# IoTKitV3th-ohneGND.net
KiCad netlist of a schematic drawn in EAGLE
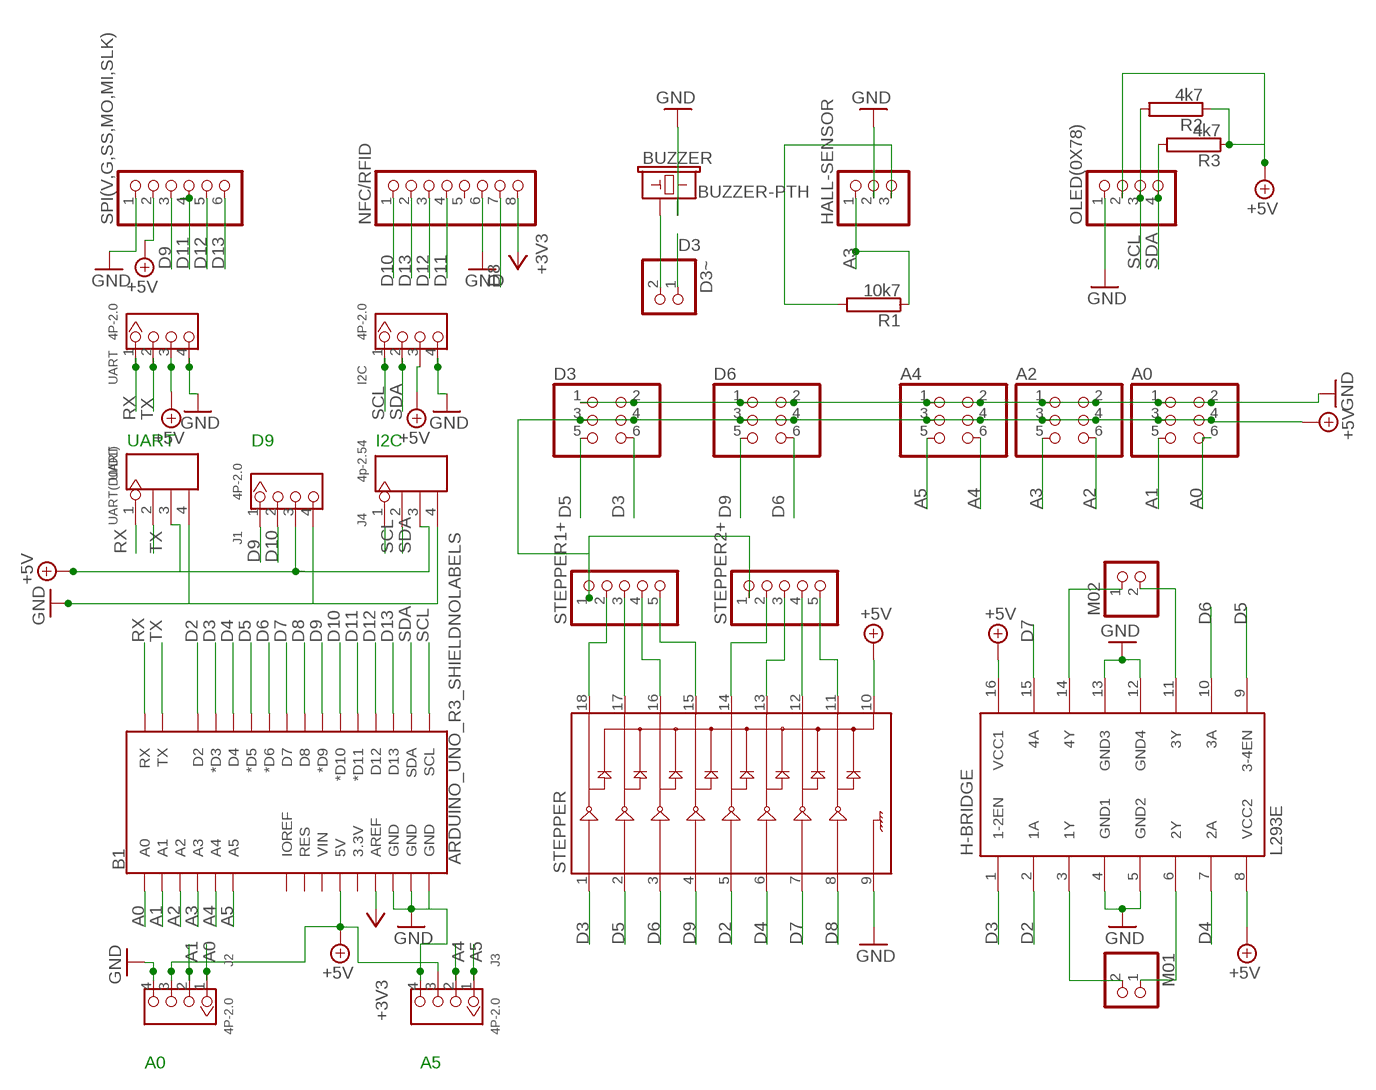
[diagram p0: schematic, sheet 1]

(export (version "E")
  (design (tool "Eeschema 10.0.6"))
  (components
    (comp (ref "A0")
      (value "PINHD-2X3")
      (footprint "eagle-import:2X03")
      (libsource (lib "eagle-import") (part "PINHD-2X3"))
    )
    (comp (ref "A2")
      (value "PINHD-2X3")
      (footprint "eagle-import:2X03")
      (libsource (lib "eagle-import") (part "PINHD-2X3"))
    )
    (comp (ref "A4")
      (value "PINHD-2X3")
      (footprint "eagle-import:2X03")
      (libsource (lib "eagle-import") (part "PINHD-2X3"))
    )
    (comp (ref "B1")
      (value "ARDUINO_UNO_R3_SHIELDNOLABELS")
      (footprint "eagle-import:UNO_R3_SHIELD_NOLABELS")
      (libsource (lib "eagle-import") (part "ARDUINO_UNO_R3_SHIELDNOLABELS"))
    )
    (comp (ref "BUZZER")
      (value "BUZZER-PTH")
      (footprint "eagle-import:BUZZER-12MM")
      (libsource (lib "eagle-import") (part "BUZZER-PTH"))
    )
    (comp (ref "D3")
      (value "PINHD-2X3")
      (footprint "eagle-import:2X03")
      (libsource (lib "eagle-import") (part "PINHD-2X3"))
    )
    (comp (ref "D3~")
      (value "PINHD-1X2")
      (footprint "eagle-import:1X02")
      (libsource (lib "eagle-import") (part "PINHD-1X2"))
    )
    (comp (ref "D6")
      (value "PINHD-2X3")
      (footprint "eagle-import:2X03")
      (libsource (lib "eagle-import") (part "PINHD-2X3"))
    )
    (comp (ref "H-BRIDGE")
      (value "L293E")
      (footprint "eagle-import:DIL16")
      (fields (field (name "MF") "Arrow Electronics"))
      (libsource (lib "eagle-import") (part "L293E"))
    )
    (comp (ref "HALL-SENSOR")
      (value "PINHD-1X3")
      (footprint "eagle-import:1X03")
      (libsource (lib "eagle-import") (part "PINHD-1X3"))
    )
    (comp (ref "I2C")
      (value "4P-2.0")
      (footprint "eagle-import:HW4-2.0")
      (libsource (lib "eagle-import") (part "GROVE-CONNECTOR-DIP(4P-2.0)"))
    )
    (comp (ref "J1")
      (value "4P-2.0")
      (footprint "eagle-import:HW4-2.0")
      (libsource (lib "eagle-import") (part "GROVE-CONNECTOR-DIP(4P-2.0)"))
    )
    (comp (ref "J2")
      (value "4P-2.0")
      (footprint "eagle-import:HW4-2.0")
      (libsource (lib "eagle-import") (part "GROVE-CONNECTOR-DIP(4P-2.0)"))
    )
    (comp (ref "J3")
      (value "4P-2.0")
      (footprint "eagle-import:HW4-2.0")
      (libsource (lib "eagle-import") (part "GROVE-CONNECTOR-DIP(4P-2.0)"))
    )
    (comp (ref "J4")
      (value "4p-2.54")
      (footprint "eagle-import:H4-2.54")
      (fields (field (name "MPN") "P125-1104A0BS116A1"))
      (libsource (lib "eagle-import") (part "DIP-BLACK-MALE-HEADER-VERT(4P-2.54)"))
    )
    (comp (ref "M01")
      (value "PINHD-1X2")
      (footprint "eagle-import:1X02")
      (libsource (lib "eagle-import") (part "PINHD-1X2"))
    )
    (comp (ref "M02")
      (value "PINHD-1X2")
      (footprint "eagle-import:1X02")
      (libsource (lib "eagle-import") (part "PINHD-1X2"))
    )
    (comp (ref "NFC/RFID")
      (value "PINHD-1X8")
      (footprint "eagle-import:1X08")
      (libsource (lib "eagle-import") (part "PINHD-1X8"))
    )
    (comp (ref "OLED(0X78)")
      (value "PINHD-1X4")
      (footprint "eagle-import:1X04")
      (libsource (lib "eagle-import") (part "PINHD-1X4"))
    )
    (comp (ref "R1")
      (value "10k7")
      (footprint "eagle-import:CA0001")
      (libsource (lib "eagle-import") (part "RCA0001"))
    )
    (comp (ref "R2")
      (value "4k7")
      (footprint "eagle-import:CA0001")
      (libsource (lib "eagle-import") (part "RCA0001"))
    )
    (comp (ref "R3")
      (value "4k7")
      (footprint "eagle-import:CA0001")
      (libsource (lib "eagle-import") (part "RCA0001"))
    )
    (comp (ref "SPI(V,G,SS,MO,MI,SLK)")
      (value "PINHD-1X6")
      (footprint "eagle-import:1X06")
      (libsource (lib "eagle-import") (part "PINHD-1X6"))
    )
    (comp (ref "STEPPER")
      (value "ULN2803DIP")
      (footprint "eagle-import:DIL18")
      (libsource (lib "eagle-import") (part "ULN2803DIP"))
    )
    (comp (ref "STEPPER1+")
      (value "PINHD-1X5")
      (footprint "eagle-import:1X05")
      (libsource (lib "eagle-import") (part "PINHD-1X5"))
    )
    (comp (ref "STEPPER2+")
      (value "PINHD-1X5")
      (footprint "eagle-import:1X05")
      (libsource (lib "eagle-import") (part "PINHD-1X5"))
    )
    (comp (ref "UART")
      (value "4P-2.0")
      (footprint "eagle-import:HW4-2.0")
      (libsource (lib "eagle-import") (part "GROVE-CONNECTOR-DIP(4P-2.0)"))
    )
    (comp (ref "UART(D0/D1)")
      (value "UART")
      (footprint "eagle-import:H4-2.54")
      (fields (field (name "MPN") "P125-1104A0BS116A1"))
      (libsource (lib "eagle-import") (part "DIP-BLACK-MALE-HEADER-VERT(4P-2.54)"))
    )
  )
  (nets
    (net (code "1") (name "+3V3") (class "Default")
      (node (ref "B1") (pin "AREF") (pinfunction "AREF_AREF") (pintype "bidirectional"))
      (node (ref "NFC/RFID") (pin "8") (pinfunction "8_8") (pintype "passive"))
    )
    (net (code "2") (name "+5V") (class "Default")
      (node (ref "A0") (pin "3") (pinfunction "3_3") (pintype "passive"))
      (node (ref "A0") (pin "4") (pinfunction "4_4") (pintype "passive"))
      (node (ref "A2") (pin "3") (pinfunction "3_3") (pintype "passive"))
      (node (ref "A2") (pin "4") (pinfunction "4_4") (pintype "passive"))
      (node (ref "A4") (pin "3") (pinfunction "3_3") (pintype "passive"))
      (node (ref "A4") (pin "4") (pinfunction "4_4") (pintype "passive"))
      (node (ref "B1") (pin "5V") (pinfunction "5V_5V") (pintype "bidirectional"))
      (node (ref "D3") (pin "3") (pinfunction "3_3") (pintype "passive"))
      (node (ref "D3") (pin "4") (pinfunction "4_4") (pintype "passive"))
      (node (ref "D6") (pin "3") (pinfunction "3_3") (pintype "passive"))
      (node (ref "D6") (pin "4") (pinfunction "4_4") (pintype "passive"))
      (node (ref "H-BRIDGE") (pin "16") (pinfunction "VCC1_16") (pintype "power_in"))
      (node (ref "H-BRIDGE") (pin "8") (pinfunction "VCC2_8") (pintype "power_in"))
      (node (ref "I2C") (pin "3") (pinfunction "3_3") (pintype "bidirectional"))
      (node (ref "J1") (pin "3") (pinfunction "3_3") (pintype "bidirectional"))
      (node (ref "J2") (pin "3") (pinfunction "3_3") (pintype "bidirectional"))
      (node (ref "J3") (pin "3") (pinfunction "3_3") (pintype "bidirectional"))
      (node (ref "J4") (pin "3") (pinfunction "P$3_3") (pintype "bidirectional"))
      (node (ref "OLED(0X78)") (pin "2") (pinfunction "2_2") (pintype "passive"))
      (node (ref "R2") (pin "1") (pinfunction "1_1") (pintype "passive"))
      (node (ref "R3") (pin "1") (pinfunction "1_1") (pintype "passive"))
      (node (ref "SPI(V,G,SS,MO,MI,SLK)") (pin "2") (pinfunction "2_2") (pintype "passive"))
      (node (ref "STEPPER") (pin "10") (pinfunction "10_10") (pintype "bidirectional"))
      (node (ref "STEPPER1+") (pin "1") (pinfunction "1_1") (pintype "passive"))
      (node (ref "STEPPER2+") (pin "1") (pinfunction "1_1") (pintype "passive"))
      (node (ref "UART") (pin "3") (pinfunction "3_3") (pintype "bidirectional"))
      (node (ref "UART(D0/D1)") (pin "3") (pinfunction "P$3_3") (pintype "bidirectional"))
    )
    (net (code "3") (name "/A0") (class "Default")
      (node (ref "A0") (pin "6") (pinfunction "6_6") (pintype "passive"))
      (node (ref "B1") (pin "A0") (pinfunction "A0_A0") (pintype "bidirectional"))
      (node (ref "J2") (pin "1") (pinfunction "1_1") (pintype "bidirectional"))
    )
    (net (code "4") (name "/A1") (class "Default")
      (node (ref "A0") (pin "5") (pinfunction "5_5") (pintype "passive"))
      (node (ref "B1") (pin "A1") (pinfunction "A1_A1") (pintype "bidirectional"))
      (node (ref "J2") (pin "2") (pinfunction "2_2") (pintype "bidirectional"))
    )
    (net (code "5") (name "/A2") (class "Default")
      (node (ref "A2") (pin "6") (pinfunction "6_6") (pintype "passive"))
      (node (ref "B1") (pin "A2") (pinfunction "A2_A2") (pintype "bidirectional"))
    )
    (net (code "6") (name "/A3") (class "Default")
      (node (ref "A2") (pin "5") (pinfunction "5_5") (pintype "passive"))
      (node (ref "B1") (pin "A3") (pinfunction "A3_A3") (pintype "bidirectional"))
      (node (ref "HALL-SENSOR") (pin "1") (pinfunction "1_1") (pintype "passive"))
      (node (ref "R1") (pin "1") (pinfunction "1_1") (pintype "passive"))
    )
    (net (code "7") (name "/A4") (class "Default")
      (node (ref "A4") (pin "6") (pinfunction "6_6") (pintype "passive"))
      (node (ref "B1") (pin "A4") (pinfunction "A4_A4") (pintype "bidirectional"))
      (node (ref "J3") (pin "2") (pinfunction "2_2") (pintype "bidirectional"))
    )
    (net (code "8") (name "/A5") (class "Default")
      (node (ref "A4") (pin "5") (pinfunction "5_5") (pintype "passive"))
      (node (ref "B1") (pin "A5") (pinfunction "A5_A5") (pintype "bidirectional"))
      (node (ref "J3") (pin "1") (pinfunction "1_1") (pintype "bidirectional"))
    )
    (net (code "9") (name "/D2") (class "Default")
      (node (ref "B1") (pin "D2") (pinfunction "D2_D2") (pintype "bidirectional"))
      (node (ref "H-BRIDGE") (pin "2") (pinfunction "1A_2") (pintype "input"))
      (node (ref "STEPPER") (pin "5") (pinfunction "5_5") (pintype "bidirectional"))
    )
    (net (code "10") (name "/D3") (class "Default")
      (node (ref "B1") (pin "D3") (pinfunction "*D3_D3") (pintype "bidirectional"))
      (node (ref "D3") (pin "6") (pinfunction "6_6") (pintype "passive"))
      (node (ref "D3~") (pin "1") (pinfunction "1_1") (pintype "passive"))
      (node (ref "H-BRIDGE") (pin "1") (pinfunction "1-2EN_1") (pintype "input"))
      (node (ref "STEPPER") (pin "1") (pinfunction "1_1") (pintype "bidirectional"))
    )
    (net (code "11") (name "/D4") (class "Default")
      (node (ref "B1") (pin "D4") (pinfunction "D4_D4") (pintype "bidirectional"))
      (node (ref "H-BRIDGE") (pin "7") (pinfunction "2A_7") (pintype "input"))
      (node (ref "STEPPER") (pin "6") (pinfunction "6_6") (pintype "bidirectional"))
    )
    (net (code "12") (name "/D5") (class "Default")
      (node (ref "B1") (pin "D5") (pinfunction "*D5_D5") (pintype "bidirectional"))
      (node (ref "D3") (pin "5") (pinfunction "5_5") (pintype "passive"))
      (node (ref "H-BRIDGE") (pin "9") (pinfunction "3-4EN_9") (pintype "input"))
      (node (ref "STEPPER") (pin "2") (pinfunction "2_2") (pintype "bidirectional"))
    )
    (net (code "13") (name "/D6") (class "Default")
      (node (ref "B1") (pin "D6") (pinfunction "*D6_D6") (pintype "bidirectional"))
      (node (ref "D6") (pin "6") (pinfunction "6_6") (pintype "passive"))
      (node (ref "H-BRIDGE") (pin "10") (pinfunction "3A_10") (pintype "input"))
      (node (ref "STEPPER") (pin "3") (pinfunction "3_3") (pintype "bidirectional"))
    )
    (net (code "14") (name "/D7") (class "Default")
      (node (ref "B1") (pin "D7") (pinfunction "D7_D7") (pintype "bidirectional"))
      (node (ref "H-BRIDGE") (pin "15") (pinfunction "4A_15") (pintype "input"))
      (node (ref "STEPPER") (pin "7") (pinfunction "7_7") (pintype "bidirectional"))
    )
    (net (code "15") (name "/D8") (class "Default")
      (node (ref "B1") (pin "D8") (pinfunction "D8_D8") (pintype "bidirectional"))
      (node (ref "NFC/RFID") (pin "7") (pinfunction "7_7") (pintype "passive"))
      (node (ref "STEPPER") (pin "8") (pinfunction "8_8") (pintype "bidirectional"))
    )
    (net (code "16") (name "/D9") (class "Default")
      (node (ref "B1") (pin "D9") (pinfunction "*D9_D9") (pintype "bidirectional"))
      (node (ref "D6") (pin "5") (pinfunction "5_5") (pintype "passive"))
      (node (ref "J1") (pin "1") (pinfunction "1_1") (pintype "bidirectional"))
      (node (ref "SPI(V,G,SS,MO,MI,SLK)") (pin "3") (pinfunction "3_3") (pintype "passive"))
      (node (ref "STEPPER") (pin "4") (pinfunction "4_4") (pintype "bidirectional"))
    )
    (net (code "17") (name "/D10") (class "Default")
      (node (ref "B1") (pin "D10") (pinfunction "*D10_D10") (pintype "bidirectional"))
      (node (ref "J1") (pin "2") (pinfunction "2_2") (pintype "bidirectional"))
      (node (ref "NFC/RFID") (pin "1") (pinfunction "1_1") (pintype "passive"))
    )
    (net (code "18") (name "/D11") (class "Default")
      (node (ref "B1") (pin "D11") (pinfunction "*D11_D11") (pintype "bidirectional"))
      (node (ref "NFC/RFID") (pin "4") (pinfunction "4_4") (pintype "passive"))
      (node (ref "SPI(V,G,SS,MO,MI,SLK)") (pin "4") (pinfunction "4_4") (pintype "passive"))
    )
    (net (code "19") (name "/D12") (class "Default")
      (node (ref "B1") (pin "D12") (pinfunction "D12_D12") (pintype "bidirectional"))
      (node (ref "NFC/RFID") (pin "3") (pinfunction "3_3") (pintype "passive"))
      (node (ref "SPI(V,G,SS,MO,MI,SLK)") (pin "5") (pinfunction "5_5") (pintype "passive"))
    )
    (net (code "20") (name "/D13") (class "Default")
      (node (ref "B1") (pin "D13") (pinfunction "D13_D13") (pintype "bidirectional"))
      (node (ref "NFC/RFID") (pin "2") (pinfunction "2_2") (pintype "passive"))
      (node (ref "SPI(V,G,SS,MO,MI,SLK)") (pin "6") (pinfunction "6_6") (pintype "passive"))
    )
    (net (code "21") (name "/RX") (class "Default")
      (node (ref "B1") (pin "RX") (pinfunction "RX_RX") (pintype "bidirectional"))
      (node (ref "UART") (pin "1") (pinfunction "1_1") (pintype "bidirectional"))
      (node (ref "UART(D0/D1)") (pin "1") (pinfunction "P$1_1") (pintype "bidirectional"))
    )
    (net (code "22") (name "/SCL") (class "Default")
      (node (ref "B1") (pin "SCL") (pinfunction "SCL_SCL") (pintype "bidirectional"))
      (node (ref "I2C") (pin "1") (pinfunction "1_1") (pintype "bidirectional"))
      (node (ref "J4") (pin "1") (pinfunction "P$1_1") (pintype "bidirectional"))
      (node (ref "OLED(0X78)") (pin "3") (pinfunction "3_3") (pintype "passive"))
      (node (ref "R2") (pin "2") (pinfunction "2_2") (pintype "passive"))
    )
    (net (code "23") (name "/SDA") (class "Default")
      (node (ref "B1") (pin "SDA") (pinfunction "SDA_SDA") (pintype "bidirectional"))
      (node (ref "I2C") (pin "2") (pinfunction "2_2") (pintype "bidirectional"))
      (node (ref "J4") (pin "2") (pinfunction "P$2_2") (pintype "bidirectional"))
      (node (ref "OLED(0X78)") (pin "4") (pinfunction "4_4") (pintype "passive"))
      (node (ref "R3") (pin "2") (pinfunction "2_2") (pintype "passive"))
    )
    (net (code "24") (name "/TX") (class "Default")
      (node (ref "B1") (pin "TX") (pinfunction "TX_TX") (pintype "bidirectional"))
      (node (ref "UART") (pin "2") (pinfunction "2_2") (pintype "bidirectional"))
      (node (ref "UART(D0/D1)") (pin "2") (pinfunction "P$2_2") (pintype "bidirectional"))
    )
    (net (code "25") (name "GND") (class "Default")
      (node (ref "A0") (pin "1") (pinfunction "1_1") (pintype "passive"))
      (node (ref "A0") (pin "2") (pinfunction "2_2") (pintype "passive"))
      (node (ref "A2") (pin "1") (pinfunction "1_1") (pintype "passive"))
      (node (ref "A2") (pin "2") (pinfunction "2_2") (pintype "passive"))
      (node (ref "A4") (pin "1") (pinfunction "1_1") (pintype "passive"))
      (node (ref "A4") (pin "2") (pinfunction "2_2") (pintype "passive"))
      (node (ref "B1") (pin "GND@0") (pinfunction "GND_GND@0") (pintype "bidirectional"))
      (node (ref "B1") (pin "GND@1") (pinfunction "GND_GND@1") (pintype "bidirectional"))
      (node (ref "B1") (pin "GND@2") (pinfunction "GND_GND@2") (pintype "bidirectional"))
      (node (ref "BUZZER") (pin "-") (pinfunction "2_-") (pintype "passive"))
      (node (ref "D3") (pin "1") (pinfunction "1_1") (pintype "passive"))
      (node (ref "D3") (pin "2") (pinfunction "2_2") (pintype "passive"))
      (node (ref "D6") (pin "1") (pinfunction "1_1") (pintype "passive"))
      (node (ref "D6") (pin "2") (pinfunction "2_2") (pintype "passive"))
      (node (ref "H-BRIDGE") (pin "12") (pinfunction "GND4_12") (pintype "power_in"))
      (node (ref "H-BRIDGE") (pin "13") (pinfunction "GND3_13") (pintype "power_in"))
      (node (ref "H-BRIDGE") (pin "4") (pinfunction "GND1_4") (pintype "power_in"))
      (node (ref "H-BRIDGE") (pin "5") (pinfunction "GND2_5") (pintype "power_in"))
      (node (ref "HALL-SENSOR") (pin "2") (pinfunction "2_2") (pintype "passive"))
      (node (ref "I2C") (pin "4") (pinfunction "4_4") (pintype "bidirectional"))
      (node (ref "J1") (pin "4") (pinfunction "4_4") (pintype "bidirectional"))
      (node (ref "J2") (pin "4") (pinfunction "4_4") (pintype "bidirectional"))
      (node (ref "J3") (pin "4") (pinfunction "4_4") (pintype "bidirectional"))
      (node (ref "J4") (pin "4") (pinfunction "P$4_4") (pintype "bidirectional"))
      (node (ref "NFC/RFID") (pin "6") (pinfunction "6_6") (pintype "passive"))
      (node (ref "OLED(0X78)") (pin "1") (pinfunction "1_1") (pintype "passive"))
      (node (ref "SPI(V,G,SS,MO,MI,SLK)") (pin "1") (pinfunction "1_1") (pintype "passive"))
      (node (ref "STEPPER") (pin "9") (pinfunction "9_9") (pintype "bidirectional"))
      (node (ref "UART") (pin "4") (pinfunction "4_4") (pintype "bidirectional"))
      (node (ref "UART(D0/D1)") (pin "4") (pinfunction "P$4_4") (pintype "bidirectional"))
    )
    (net (code "26") (name "Net-(BUZZER-1)") (class "Default")
      (node (ref "BUZZER") (pin "+") (pinfunction "1_+") (pintype "passive"))
      (node (ref "D3~") (pin "2") (pinfunction "2_2") (pintype "passive"))
    )
    (net (code "27") (name "Net-(H-BRIDGE-1Y)") (class "Default")
      (node (ref "H-BRIDGE") (pin "3") (pinfunction "1Y_3") (pintype "output"))
      (node (ref "M01") (pin "2") (pinfunction "2_2") (pintype "passive"))
    )
    (net (code "28") (name "Net-(H-BRIDGE-2Y)") (class "Default")
      (node (ref "H-BRIDGE") (pin "6") (pinfunction "2Y_6") (pintype "output"))
      (node (ref "M01") (pin "1") (pinfunction "1_1") (pintype "passive"))
    )
    (net (code "29") (name "Net-(H-BRIDGE-3Y)") (class "Default")
      (node (ref "H-BRIDGE") (pin "11") (pinfunction "3Y_11") (pintype "output"))
      (node (ref "M02") (pin "2") (pinfunction "2_2") (pintype "passive"))
    )
    (net (code "30") (name "Net-(H-BRIDGE-4Y)") (class "Default")
      (node (ref "H-BRIDGE") (pin "14") (pinfunction "4Y_14") (pintype "output"))
      (node (ref "M02") (pin "1") (pinfunction "1_1") (pintype "passive"))
    )
    (net (code "31") (name "Net-(HALL-SENSOR-Pad3)") (class "Default")
      (node (ref "HALL-SENSOR") (pin "3") (pinfunction "3_3") (pintype "passive"))
      (node (ref "R1") (pin "2") (pinfunction "2_2") (pintype "passive"))
    )
    (net (code "32") (name "Net-(STEPPER-Pad11)") (class "Default")
      (node (ref "STEPPER") (pin "11") (pinfunction "11_11") (pintype "bidirectional"))
      (node (ref "STEPPER2+") (pin "5") (pinfunction "5_5") (pintype "passive"))
    )
    (net (code "33") (name "Net-(STEPPER-Pad12)") (class "Default")
      (node (ref "STEPPER") (pin "12") (pinfunction "12_12") (pintype "bidirectional"))
      (node (ref "STEPPER2+") (pin "4") (pinfunction "4_4") (pintype "passive"))
    )
    (net (code "34") (name "Net-(STEPPER-Pad13)") (class "Default")
      (node (ref "STEPPER") (pin "13") (pinfunction "13_13") (pintype "bidirectional"))
      (node (ref "STEPPER2+") (pin "3") (pinfunction "3_3") (pintype "passive"))
    )
    (net (code "35") (name "Net-(STEPPER-Pad14)") (class "Default")
      (node (ref "STEPPER") (pin "14") (pinfunction "14_14") (pintype "bidirectional"))
      (node (ref "STEPPER2+") (pin "2") (pinfunction "2_2") (pintype "passive"))
    )
    (net (code "36") (name "Net-(STEPPER-Pad15)") (class "Default")
      (node (ref "STEPPER") (pin "15") (pinfunction "15_15") (pintype "bidirectional"))
      (node (ref "STEPPER1+") (pin "5") (pinfunction "5_5") (pintype "passive"))
    )
    (net (code "37") (name "Net-(STEPPER-Pad16)") (class "Default")
      (node (ref "STEPPER") (pin "16") (pinfunction "16_16") (pintype "bidirectional"))
      (node (ref "STEPPER1+") (pin "4") (pinfunction "4_4") (pintype "passive"))
    )
    (net (code "38") (name "Net-(STEPPER-Pad17)") (class "Default")
      (node (ref "STEPPER") (pin "17") (pinfunction "17_17") (pintype "bidirectional"))
      (node (ref "STEPPER1+") (pin "3") (pinfunction "3_3") (pintype "passive"))
    )
    (net (code "39") (name "Net-(STEPPER-Pad18)") (class "Default")
      (node (ref "STEPPER") (pin "18") (pinfunction "18_18") (pintype "bidirectional"))
      (node (ref "STEPPER1+") (pin "2") (pinfunction "2_2") (pintype "passive"))
    )
    (net (code "40") (name "unconnected-(B1-Pad3.3V)") (class "Default")
      (node (ref "B1") (pin "3.3V") (pinfunction "3.3V_3.3V") (pintype "bidirectional"))
    )
    (net (code "41") (name "unconnected-(B1-PadIOREF)") (class "Default")
      (node (ref "B1") (pin "IOREF") (pinfunction "IOREF_IOREF") (pintype "bidirectional"))
    )
    (net (code "42") (name "unconnected-(B1-PadRES)") (class "Default")
      (node (ref "B1") (pin "RES") (pinfunction "RES_RES") (pintype "bidirectional"))
    )
    (net (code "43") (name "unconnected-(B1-PadVIN)") (class "Default")
      (node (ref "B1") (pin "VIN") (pinfunction "VIN_VIN") (pintype "bidirectional"))
    )
    (net (code "44") (name "unconnected-(NFC/RFID-Pad5)") (class "Default")
      (node (ref "NFC/RFID") (pin "5") (pinfunction "5_5") (pintype "passive"))
    )
  )
)
